# SRG_1_0.net
KiCad netlist of a schematic drawn in EAGLE
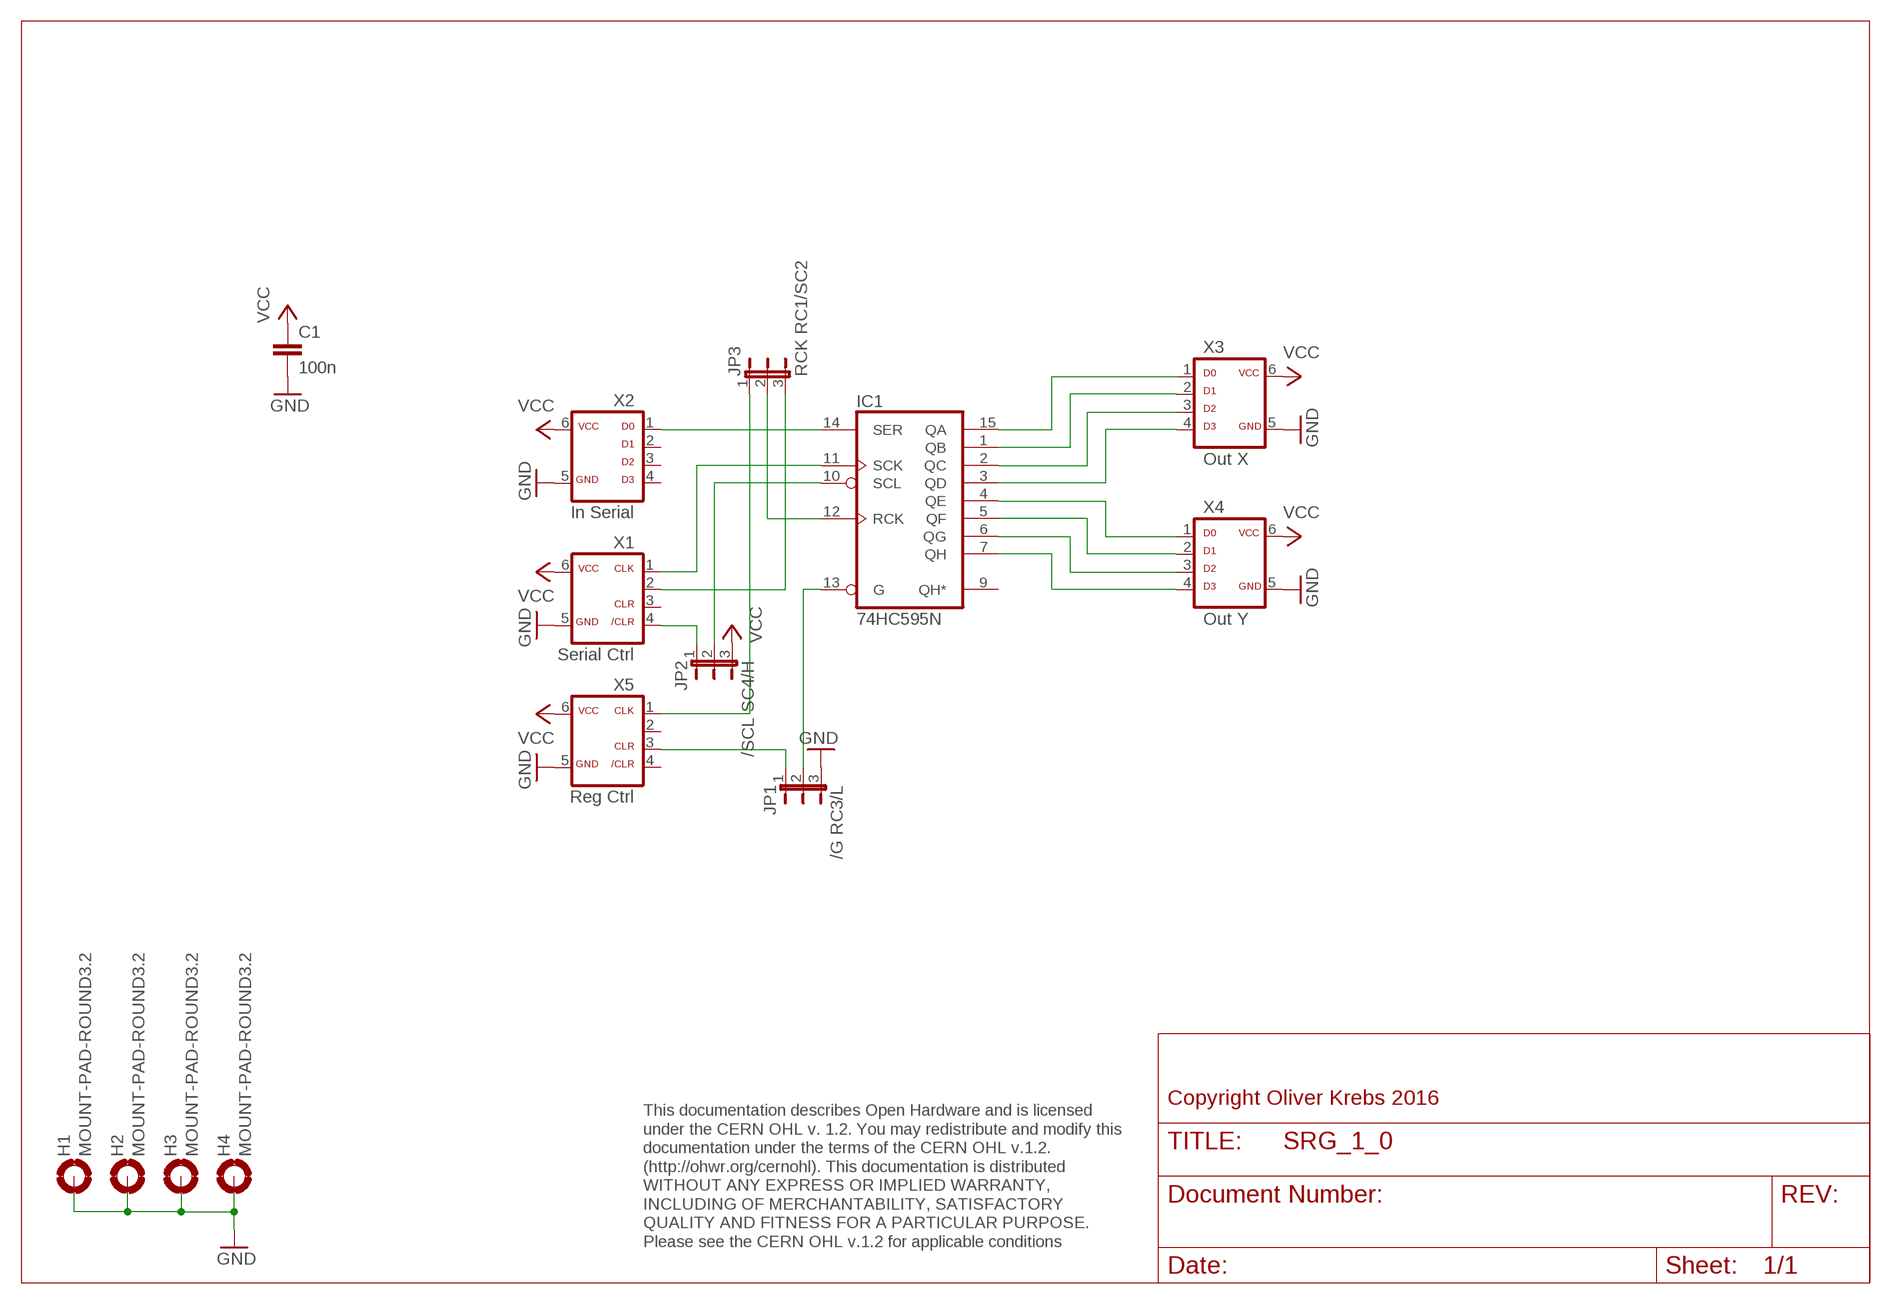
[diagram p0: schematic, sheet 1]

(export (version "E")
  (design (tool "Eeschema 10.0.6"))
  (components
    (comp (ref "C1")
      (value "100n")
      (footprint "eagle-import:C050-025X075")
      (libsource (lib "eagle-import") (part "C-EU050-025X075"))
    )
    (comp (ref "H1")
      (value "MOUNT-PAD-ROUND3.2")
      (footprint "eagle-import:3,2-PAD")
      (libsource (lib "eagle-import") (part "MOUNT-PAD-ROUND3.2"))
    )
    (comp (ref "H2")
      (value "MOUNT-PAD-ROUND3.2")
      (footprint "eagle-import:3,2-PAD")
      (libsource (lib "eagle-import") (part "MOUNT-PAD-ROUND3.2"))
    )
    (comp (ref "H3")
      (value "MOUNT-PAD-ROUND3.2")
      (footprint "eagle-import:3,2-PAD")
      (libsource (lib "eagle-import") (part "MOUNT-PAD-ROUND3.2"))
    )
    (comp (ref "H4")
      (value "MOUNT-PAD-ROUND3.2")
      (footprint "eagle-import:3,2-PAD")
      (libsource (lib "eagle-import") (part "MOUNT-PAD-ROUND3.2"))
    )
    (comp (ref "IC1")
      (value "74HC595N")
      (footprint "eagle-import:DIL16")
      (libsource (lib "eagle-import") (part "74595NHC"))
    )
    (comp (ref "JP1")
      (value "/G RC3/L")
      (footprint "eagle-import:JP2-U")
      (libsource (lib "eagle-import") (part "JP2EJP2-U"))
    )
    (comp (ref "JP2")
      (value "/SCL SC4/H")
      (footprint "eagle-import:JP2-U")
      (libsource (lib "eagle-import") (part "JP2EJP2-U"))
    )
    (comp (ref "JP3")
      (value "RCK RC1/SC2")
      (footprint "eagle-import:JP2-U")
      (libsource (lib "eagle-import") (part "JP2EJP2-U"))
    )
    (comp (ref "X1")
      (value "Serial Ctrl")
      (footprint "eagle-import:ML-6")
      (libsource (lib "eagle-import") (part "ML6C"))
    )
    (comp (ref "X2")
      (value "In Serial")
      (footprint "eagle-import:ML-6")
      (libsource (lib "eagle-import") (part "ML6D"))
    )
    (comp (ref "X3")
      (value "Out X")
      (footprint "eagle-import:ML-6")
      (libsource (lib "eagle-import") (part "ML6D"))
    )
    (comp (ref "X4")
      (value "Out Y")
      (footprint "eagle-import:ML-6")
      (libsource (lib "eagle-import") (part "ML6D"))
    )
    (comp (ref "X5")
      (value "Reg Ctrl")
      (footprint "eagle-import:ML-6")
      (libsource (lib "eagle-import") (part "ML6C"))
    )
  )
  (nets
    (net (code "1") (name "GND") (class "Default")
      (node (ref "C1") (pin "2") (pinfunction "2_2") (pintype "passive"))
      (node (ref "H1") (pin "B3,2") (pinfunction "MOUNT_B3,2") (pintype "passive"))
      (node (ref "H2") (pin "B3,2") (pinfunction "MOUNT_B3,2") (pintype "passive"))
      (node (ref "H3") (pin "B3,2") (pinfunction "MOUNT_B3,2") (pintype "passive"))
      (node (ref "H4") (pin "B3,2") (pinfunction "MOUNT_B3,2") (pintype "passive"))
      (node (ref "JP1") (pin "3") (pinfunction "3_3") (pintype "passive"))
      (node (ref "X1") (pin "5") (pinfunction "5_5") (pintype "passive"))
      (node (ref "X2") (pin "5") (pinfunction "5_5") (pintype "passive"))
      (node (ref "X3") (pin "5") (pinfunction "5_5") (pintype "passive"))
      (node (ref "X4") (pin "5") (pinfunction "5_5") (pintype "passive"))
      (node (ref "X5") (pin "5") (pinfunction "5_5") (pintype "passive"))
    )
    (net (code "2") (name "Net-(IC1A-G)") (class "Default")
      (node (ref "IC1") (pin "13") (pinfunction "G_13") (pintype "input"))
      (node (ref "JP1") (pin "2") (pinfunction "2_2") (pintype "passive"))
    )
    (net (code "3") (name "Net-(IC1A-QA)") (class "Default")
      (node (ref "IC1") (pin "15") (pinfunction "QA_15") (pintype "tri_state"))
      (node (ref "X3") (pin "1") (pinfunction "1_1") (pintype "passive"))
    )
    (net (code "4") (name "Net-(IC1A-QB)") (class "Default")
      (node (ref "IC1") (pin "1") (pinfunction "QB_1") (pintype "tri_state"))
      (node (ref "X3") (pin "2") (pinfunction "2_2") (pintype "passive"))
    )
    (net (code "5") (name "Net-(IC1A-QC)") (class "Default")
      (node (ref "IC1") (pin "2") (pinfunction "QC_2") (pintype "tri_state"))
      (node (ref "X3") (pin "3") (pinfunction "3_3") (pintype "passive"))
    )
    (net (code "6") (name "Net-(IC1A-QD)") (class "Default")
      (node (ref "IC1") (pin "3") (pinfunction "QD_3") (pintype "tri_state"))
      (node (ref "X3") (pin "4") (pinfunction "4_4") (pintype "passive"))
    )
    (net (code "7") (name "Net-(IC1A-QE)") (class "Default")
      (node (ref "IC1") (pin "4") (pinfunction "QE_4") (pintype "tri_state"))
      (node (ref "X4") (pin "1") (pinfunction "1_1") (pintype "passive"))
    )
    (net (code "8") (name "Net-(IC1A-QF)") (class "Default")
      (node (ref "IC1") (pin "5") (pinfunction "QF_5") (pintype "tri_state"))
      (node (ref "X4") (pin "2") (pinfunction "2_2") (pintype "passive"))
    )
    (net (code "9") (name "Net-(IC1A-QG)") (class "Default")
      (node (ref "IC1") (pin "6") (pinfunction "QG_6") (pintype "tri_state"))
      (node (ref "X4") (pin "3") (pinfunction "3_3") (pintype "passive"))
    )
    (net (code "10") (name "Net-(IC1A-QH)") (class "Default")
      (node (ref "IC1") (pin "7") (pinfunction "QH_7") (pintype "tri_state"))
      (node (ref "X4") (pin "4") (pinfunction "4_4") (pintype "passive"))
    )
    (net (code "11") (name "Net-(IC1A-RCK)") (class "Default")
      (node (ref "IC1") (pin "12") (pinfunction "RCK_12") (pintype "input"))
      (node (ref "JP3") (pin "2") (pinfunction "2_2") (pintype "passive"))
    )
    (net (code "12") (name "Net-(IC1A-SCK)") (class "Default")
      (node (ref "IC1") (pin "11") (pinfunction "SCK_11") (pintype "input"))
      (node (ref "X1") (pin "1") (pinfunction "1_1") (pintype "passive"))
    )
    (net (code "13") (name "Net-(IC1A-SCL)") (class "Default")
      (node (ref "IC1") (pin "10") (pinfunction "SCL_10") (pintype "input"))
      (node (ref "JP2") (pin "2") (pinfunction "2_2") (pintype "passive"))
    )
    (net (code "14") (name "Net-(IC1A-SER)") (class "Default")
      (node (ref "IC1") (pin "14") (pinfunction "SER_14") (pintype "input"))
      (node (ref "X2") (pin "1") (pinfunction "1_1") (pintype "passive"))
    )
    (net (code "15") (name "Net-(JP1-Pad1)") (class "Default")
      (node (ref "JP1") (pin "1") (pinfunction "1_1") (pintype "passive"))
      (node (ref "X5") (pin "3") (pinfunction "3_3") (pintype "passive"))
    )
    (net (code "16") (name "Net-(JP2-Pad1)") (class "Default")
      (node (ref "JP2") (pin "1") (pinfunction "1_1") (pintype "passive"))
      (node (ref "X1") (pin "4") (pinfunction "4_4") (pintype "passive"))
    )
    (net (code "17") (name "Net-(JP3-Pad1)") (class "Default")
      (node (ref "JP3") (pin "1") (pinfunction "1_1") (pintype "passive"))
      (node (ref "X5") (pin "1") (pinfunction "1_1") (pintype "passive"))
    )
    (net (code "18") (name "Net-(JP3-Pad3)") (class "Default")
      (node (ref "JP3") (pin "3") (pinfunction "3_3") (pintype "passive"))
      (node (ref "X1") (pin "2") (pinfunction "2_2") (pintype "passive"))
    )
    (net (code "19") (name "VCC") (class "Default")
      (node (ref "C1") (pin "1") (pinfunction "1_1") (pintype "passive"))
      (node (ref "JP2") (pin "3") (pinfunction "3_3") (pintype "passive"))
      (node (ref "X1") (pin "6") (pinfunction "6_6") (pintype "passive"))
      (node (ref "X2") (pin "6") (pinfunction "6_6") (pintype "passive"))
      (node (ref "X3") (pin "6") (pinfunction "6_6") (pintype "passive"))
      (node (ref "X4") (pin "6") (pinfunction "6_6") (pintype "passive"))
      (node (ref "X5") (pin "6") (pinfunction "6_6") (pintype "passive"))
    )
    (net (code "20") (name "unconnected-(IC1A-QH*-Pad9)") (class "Default")
      (node (ref "IC1") (pin "9") (pinfunction "QH*_9") (pintype "tri_state"))
    )
    (net (code "21") (name "unconnected-(X1-Pad3)") (class "Default")
      (node (ref "X1") (pin "3") (pinfunction "3_3") (pintype "passive"))
    )
    (net (code "22") (name "unconnected-(X2-Pad2)") (class "Default")
      (node (ref "X2") (pin "2") (pinfunction "2_2") (pintype "passive"))
    )
    (net (code "23") (name "unconnected-(X2-Pad3)") (class "Default")
      (node (ref "X2") (pin "3") (pinfunction "3_3") (pintype "passive"))
    )
    (net (code "24") (name "unconnected-(X2-Pad4)") (class "Default")
      (node (ref "X2") (pin "4") (pinfunction "4_4") (pintype "passive"))
    )
    (net (code "25") (name "unconnected-(X5-Pad2)") (class "Default")
      (node (ref "X5") (pin "2") (pinfunction "2_2") (pintype "passive"))
    )
    (net (code "26") (name "unconnected-(X5-Pad4)") (class "Default")
      (node (ref "X5") (pin "4") (pinfunction "4_4") (pintype "passive"))
    )
  )
)
